# LazuriteBLE_rev1.net
KiCad netlist of a schematic drawn in EAGLE
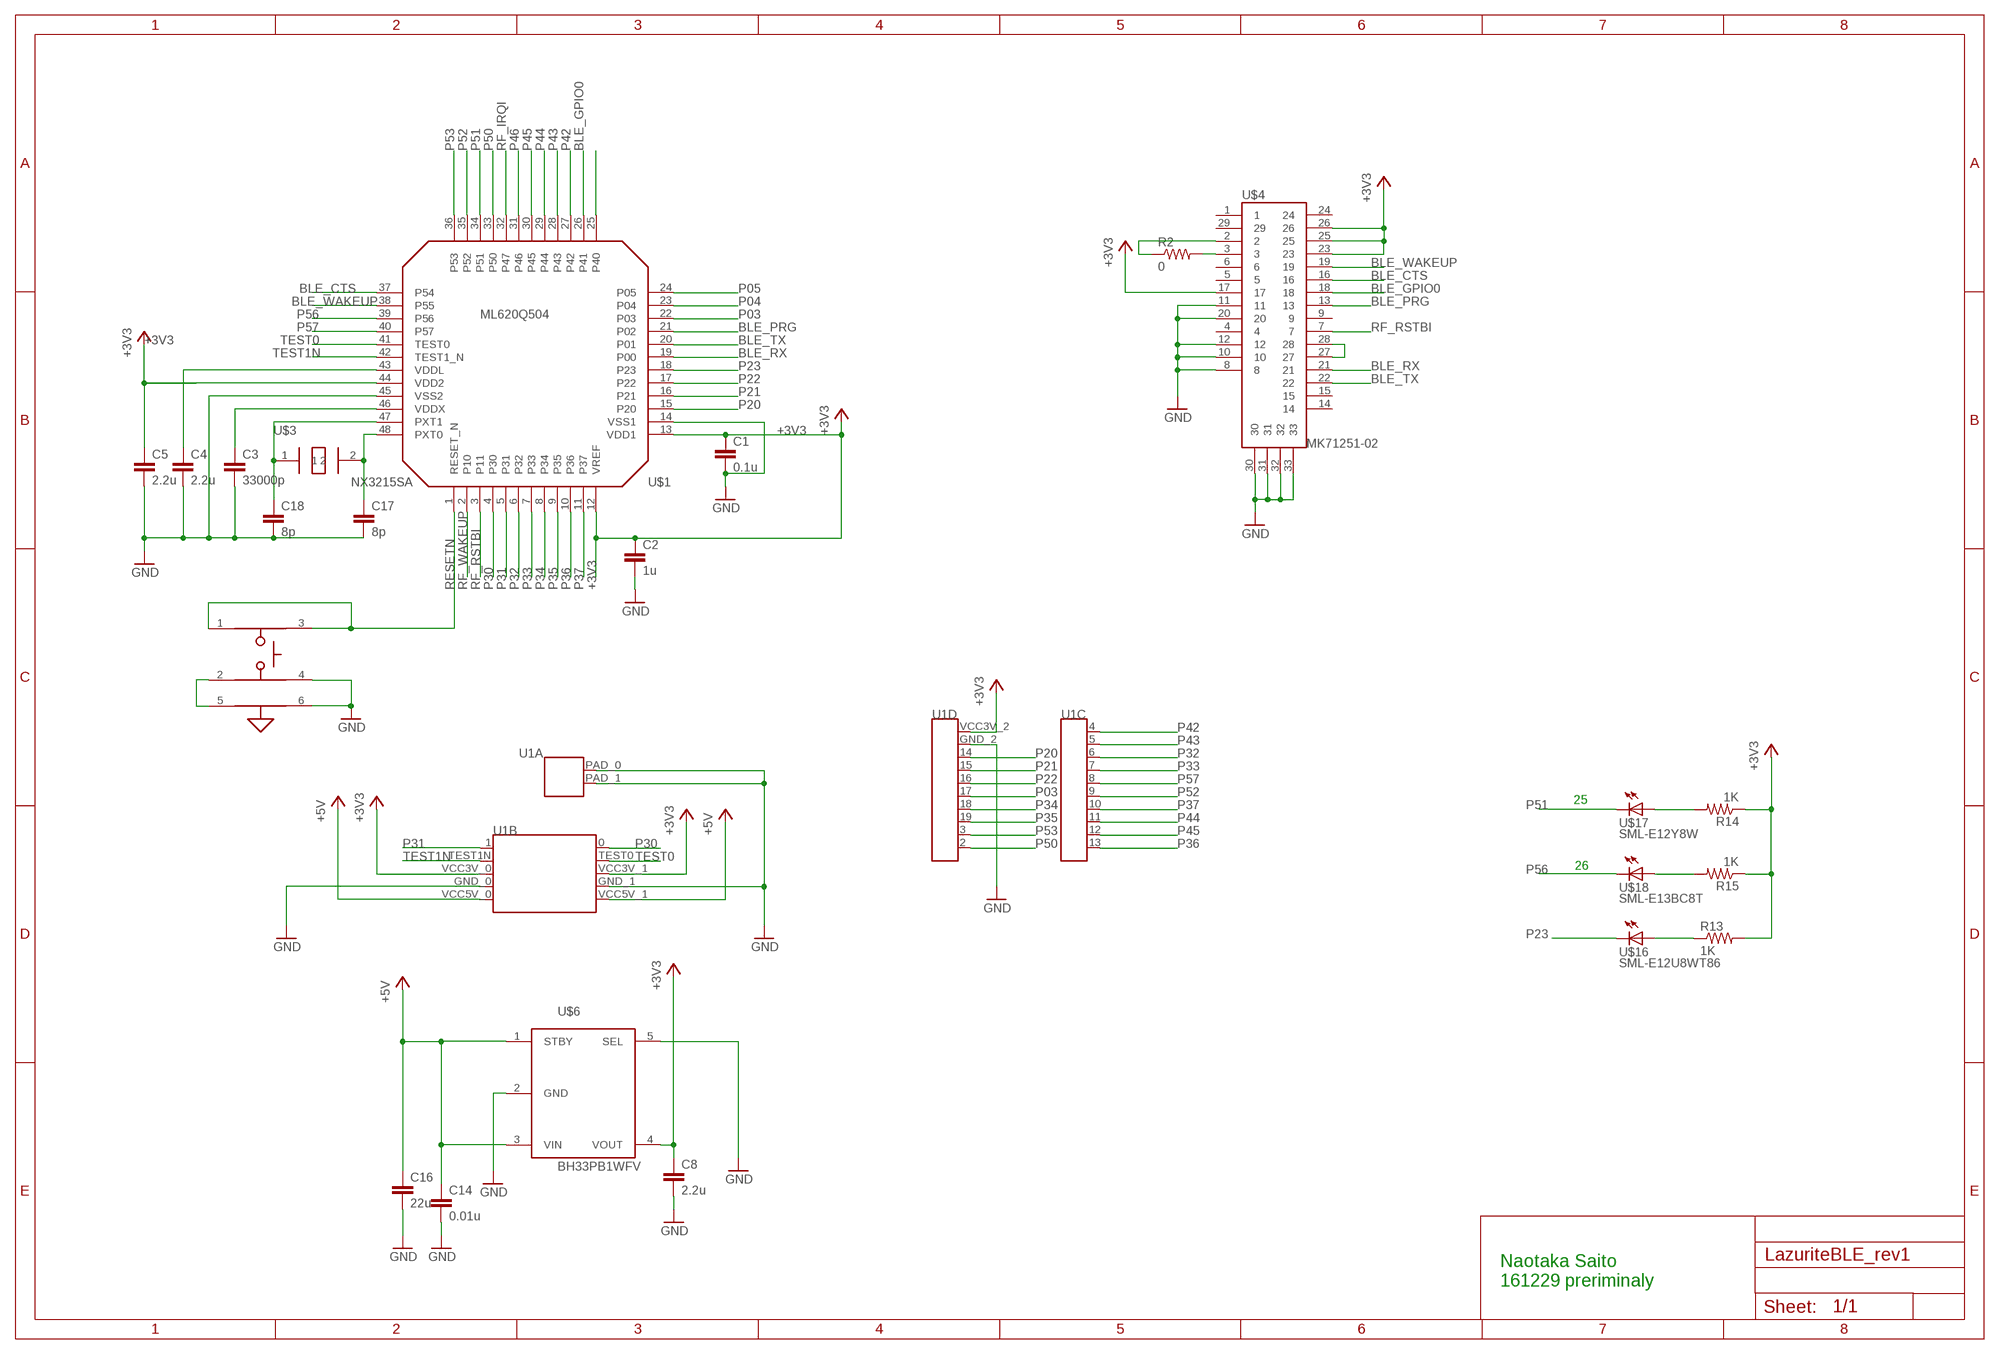
[diagram p0: schematic, sheet 1]

(export (version "E")
  (design (tool "Eeschema 10.0.6"))
  (components
    (comp (ref "C1")
      (value "0.1u")
      (footprint "eagle-import:C0402")
      (libsource (lib "eagle-import") (part "C-EUC0402"))
    )
    (comp (ref "C2")
      (value "1u")
      (footprint "eagle-import:C0402")
      (libsource (lib "eagle-import") (part "C-EUC0402"))
    )
    (comp (ref "C3")
      (value "33000p")
      (footprint "eagle-import:C0402")
      (libsource (lib "eagle-import") (part "C-EUC0402"))
    )
    (comp (ref "C4")
      (value "2.2u")
      (footprint "eagle-import:C0402")
      (libsource (lib "eagle-import") (part "C-EUC0402"))
    )
    (comp (ref "C5")
      (value "2.2u")
      (footprint "eagle-import:C0402")
      (libsource (lib "eagle-import") (part "C-EUC0402"))
    )
    (comp (ref "C8")
      (value "2.2u")
      (footprint "eagle-import:C0402")
      (libsource (lib "eagle-import") (part "C-EUC0402"))
    )
    (comp (ref "C14")
      (value "0.01u")
      (footprint "eagle-import:C0402")
      (libsource (lib "eagle-import") (part "C-EUC0402"))
    )
    (comp (ref "C16")
      (value "22u")
      (footprint "eagle-import:C1206")
      (libsource (lib "eagle-import") (part "C-EUC1206"))
    )
    (comp (ref "C17")
      (value "8p")
      (footprint "eagle-import:C0402")
      (libsource (lib "eagle-import") (part "C-EUC0402"))
    )
    (comp (ref "C18")
      (value "8p")
      (footprint "eagle-import:C0402")
      (libsource (lib "eagle-import") (part "C-EUC0402"))
    )
    (comp (ref "R2")
      (value "0")
      (footprint "eagle-import:R0402")
      (libsource (lib "eagle-import") (part "R-US_R0402"))
    )
    (comp (ref "R13")
      (value "1K")
      (footprint "eagle-import:R0402")
      (libsource (lib "eagle-import") (part "R-US_R0402"))
    )
    (comp (ref "R14")
      (value "1K")
      (footprint "eagle-import:R0402")
      (libsource (lib "eagle-import") (part "R-US_R0402"))
    )
    (comp (ref "R15")
      (value "1K")
      (footprint "eagle-import:R0402")
      (libsource (lib "eagle-import") (part "R-US_R0402"))
    )
    (comp (ref "SW1")
      (value "SKSGACE010")
      (footprint "eagle-import:SKSGACE010")
      (libsource (lib "eagle-import") (part "SKSGACE010"))
    )
    (comp (ref "U$1")
      (value "ML620Q504")
      (footprint "eagle-import:ML620Q504")
      (libsource (lib "eagle-import") (part "ML620Q504"))
    )
    (comp (ref "U$3")
      (value "NX3215SA")
      (footprint "eagle-import:NX3215SA-32,768K-SFD-MUA-14")
      (libsource (lib "eagle-import") (part "NX3215SA"))
    )
    (comp (ref "U$4")
      (value "MK71251-02")
      (footprint "eagle-import:MK71251-02")
      (libsource (lib "eagle-import") (part "MK71251-02"))
    )
    (comp (ref "U$6")
      (value "BH33PB1WFV")
      (footprint "eagle-import:HVSOF5")
      (libsource (lib "eagle-import") (part "BHXXPB1WFV"))
    )
    (comp (ref "U$16")
      (value "SML-E12U8WT86")
      (footprint "eagle-import:SML-E1X")
      (libsource (lib "eagle-import") (part "SML-E1X"))
    )
    (comp (ref "U$17")
      (value "SML-E12Y8W")
      (footprint "eagle-import:SML-E1X")
      (libsource (lib "eagle-import") (part "SML-E1X"))
    )
    (comp (ref "U$18")
      (value "SML-E13BC8T")
      (footprint "eagle-import:SML-E1X")
      (libsource (lib "eagle-import") (part "SML-E1X"))
    )
    (comp (ref "U1")
      (value "LAZURITE920J")
      (footprint "eagle-import:LAZURITE920J2")
      (libsource (lib "eagle-import") (part "LAZURITE920J"))
    )
  )
  (nets
    (net (code "1") (name "+3V3") (class "Default")
      (node (ref "C1") (pin "1") (pinfunction "1_1") (pintype "passive"))
      (node (ref "C2") (pin "1") (pinfunction "1_1") (pintype "passive"))
      (node (ref "C5") (pin "1") (pinfunction "1_1") (pintype "passive"))
      (node (ref "C8") (pin "1") (pinfunction "1_1") (pintype "passive"))
      (node (ref "R13") (pin "2") (pinfunction "2_2") (pintype "passive"))
      (node (ref "R14") (pin "1") (pinfunction "1_1") (pintype "passive"))
      (node (ref "R15") (pin "1") (pinfunction "1_1") (pintype "passive"))
      (node (ref "U$1") (pin "12") (pinfunction "VREF_12") (pintype "bidirectional"))
      (node (ref "U$1") (pin "13") (pinfunction "VDD1_13") (pintype "bidirectional"))
      (node (ref "U$1") (pin "44") (pinfunction "VDD2_44") (pintype "bidirectional"))
      (node (ref "U$4") (pin "17") (pinfunction "17_17") (pintype "power_in"))
      (node (ref "U$4") (pin "23") (pinfunction "23_23") (pintype "bidirectional"))
      (node (ref "U$4") (pin "25") (pinfunction "25_25") (pintype "bidirectional"))
      (node (ref "U$4") (pin "26") (pinfunction "26_26") (pintype "bidirectional"))
      (node (ref "U$6") (pin "4") (pinfunction "VOUT_4") (pintype "bidirectional"))
      (node (ref "U1") (pin "VCC3V_0") (pinfunction "VCC3V_0_VCC3V_0") (pintype "passive"))
      (node (ref "U1") (pin "VCC3V_1") (pinfunction "VCC3V_1_VCC3V_1") (pintype "passive"))
      (node (ref "U1") (pin "VCC3V_2") (pinfunction "VCC3V_2_VCC3V_2") (pintype "passive"))
    )
    (net (code "2") (name "+5V") (class "Default")
      (node (ref "C14") (pin "1") (pinfunction "1_1") (pintype "passive"))
      (node (ref "C16") (pin "1") (pinfunction "1_1") (pintype "passive"))
      (node (ref "U$6") (pin "1") (pinfunction "STBY_1") (pintype "bidirectional"))
      (node (ref "U$6") (pin "3") (pinfunction "VIN_3") (pintype "bidirectional"))
      (node (ref "U1") (pin "VCC5V_0") (pinfunction "VCC5V_0_VCC5V_0") (pintype "passive"))
      (node (ref "U1") (pin "VCC5V_1") (pinfunction "VCC5V_1_VCC5V_1") (pintype "passive"))
    )
    (net (code "3") (name "/BLE_CTS") (class "Default")
      (node (ref "U$1") (pin "37") (pinfunction "P54_37") (pintype "bidirectional"))
      (node (ref "U$4") (pin "16") (pinfunction "16_16") (pintype "bidirectional"))
    )
    (net (code "4") (name "/BLE_GPIO0") (class "Default")
      (node (ref "U$1") (pin "26") (pinfunction "P41_26") (pintype "bidirectional"))
      (node (ref "U$4") (pin "18") (pinfunction "18_18") (pintype "bidirectional"))
    )
    (net (code "5") (name "/BLE_PRG") (class "Default")
      (node (ref "U$1") (pin "21") (pinfunction "P02_21") (pintype "bidirectional"))
      (node (ref "U$4") (pin "13") (pinfunction "13_13") (pintype "bidirectional"))
    )
    (net (code "6") (name "/BLE_RX") (class "Default")
      (node (ref "U$1") (pin "19") (pinfunction "P00_19") (pintype "bidirectional"))
      (node (ref "U$4") (pin "21") (pinfunction "21_21") (pintype "bidirectional"))
    )
    (net (code "7") (name "/BLE_TX") (class "Default")
      (node (ref "U$1") (pin "20") (pinfunction "P01_20") (pintype "bidirectional"))
      (node (ref "U$4") (pin "22") (pinfunction "22_22") (pintype "bidirectional"))
    )
    (net (code "8") (name "/BLE_WAKEUP") (class "Default")
      (node (ref "U$1") (pin "38") (pinfunction "P55_38") (pintype "bidirectional"))
      (node (ref "U$4") (pin "19") (pinfunction "19_19") (pintype "input"))
    )
    (net (code "9") (name "/P03") (class "Default")
      (node (ref "U$1") (pin "22") (pinfunction "P03_22") (pintype "bidirectional"))
      (node (ref "U1") (pin "17") (pinfunction "17_17") (pintype "passive"))
    )
    (net (code "10") (name "/P04") (class "Default")
      (node (ref "U$1") (pin "23") (pinfunction "P04_23") (pintype "bidirectional"))
    )
    (net (code "11") (name "/P05") (class "Default")
      (node (ref "U$1") (pin "24") (pinfunction "P05_24") (pintype "bidirectional"))
    )
    (net (code "12") (name "/P20") (class "Default")
      (node (ref "U$1") (pin "15") (pinfunction "P20_15") (pintype "bidirectional"))
      (node (ref "U1") (pin "14") (pinfunction "14_14") (pintype "passive"))
    )
    (net (code "13") (name "/P21") (class "Default")
      (node (ref "U$1") (pin "16") (pinfunction "P21_16") (pintype "bidirectional"))
      (node (ref "U1") (pin "15") (pinfunction "15_15") (pintype "passive"))
    )
    (net (code "14") (name "/P22") (class "Default")
      (node (ref "U$1") (pin "17") (pinfunction "P22_17") (pintype "bidirectional"))
      (node (ref "U1") (pin "16") (pinfunction "16_16") (pintype "passive"))
    )
    (net (code "15") (name "/P23") (class "Default")
      (node (ref "U$1") (pin "18") (pinfunction "P23_18") (pintype "bidirectional"))
      (node (ref "U$16") (pin "C") (pinfunction "C_C") (pintype "passive"))
    )
    (net (code "16") (name "/P30") (class "Default")
      (node (ref "U$1") (pin "4") (pinfunction "P30_4") (pintype "bidirectional"))
      (node (ref "U1") (pin "0") (pinfunction "0_0") (pintype "passive"))
    )
    (net (code "17") (name "/P31") (class "Default")
      (node (ref "U$1") (pin "5") (pinfunction "P31_5") (pintype "bidirectional"))
      (node (ref "U1") (pin "1") (pinfunction "1_1") (pintype "passive"))
    )
    (net (code "18") (name "/P32") (class "Default")
      (node (ref "U$1") (pin "6") (pinfunction "P32_6") (pintype "bidirectional"))
      (node (ref "U1") (pin "6") (pinfunction "6_6") (pintype "passive"))
    )
    (net (code "19") (name "/P33") (class "Default")
      (node (ref "U$1") (pin "7") (pinfunction "P33_7") (pintype "bidirectional"))
      (node (ref "U1") (pin "7") (pinfunction "7_7") (pintype "passive"))
    )
    (net (code "20") (name "/P34") (class "Default")
      (node (ref "U$1") (pin "8") (pinfunction "P34_8") (pintype "bidirectional"))
      (node (ref "U1") (pin "18") (pinfunction "18_18") (pintype "passive"))
    )
    (net (code "21") (name "/P35") (class "Default")
      (node (ref "U$1") (pin "9") (pinfunction "P35_9") (pintype "bidirectional"))
      (node (ref "U1") (pin "19") (pinfunction "19_19") (pintype "passive"))
    )
    (net (code "22") (name "/P36") (class "Default")
      (node (ref "U$1") (pin "10") (pinfunction "P36_10") (pintype "bidirectional"))
      (node (ref "U1") (pin "13") (pinfunction "13_13") (pintype "passive"))
    )
    (net (code "23") (name "/P37") (class "Default")
      (node (ref "U$1") (pin "11") (pinfunction "P37_11") (pintype "bidirectional"))
      (node (ref "U1") (pin "10") (pinfunction "10_10") (pintype "passive"))
    )
    (net (code "24") (name "/P42") (class "Default")
      (node (ref "U$1") (pin "27") (pinfunction "P42_27") (pintype "bidirectional"))
      (node (ref "U1") (pin "4") (pinfunction "4_4") (pintype "passive"))
    )
    (net (code "25") (name "/P43") (class "Default")
      (node (ref "U$1") (pin "28") (pinfunction "P43_28") (pintype "bidirectional"))
      (node (ref "U1") (pin "5") (pinfunction "5_5") (pintype "passive"))
    )
    (net (code "26") (name "/P44") (class "Default")
      (node (ref "U$1") (pin "29") (pinfunction "P44_29") (pintype "bidirectional"))
      (node (ref "U1") (pin "11") (pinfunction "11_11") (pintype "passive"))
    )
    (net (code "27") (name "/P45") (class "Default")
      (node (ref "U$1") (pin "30") (pinfunction "P45_30") (pintype "bidirectional"))
      (node (ref "U1") (pin "12") (pinfunction "12_12") (pintype "passive"))
    )
    (net (code "28") (name "/P46") (class "Default")
      (node (ref "U$1") (pin "31") (pinfunction "P46_31") (pintype "bidirectional"))
    )
    (net (code "29") (name "/P50") (class "Default")
      (node (ref "U$1") (pin "33") (pinfunction "P50_33") (pintype "bidirectional"))
      (node (ref "U1") (pin "2") (pinfunction "2_2") (pintype "passive"))
    )
    (net (code "30") (name "/P51") (class "Default")
      (node (ref "U$1") (pin "34") (pinfunction "P51_34") (pintype "bidirectional"))
      (node (ref "U$17") (pin "C") (pinfunction "C_C") (pintype "passive"))
    )
    (net (code "31") (name "/P52") (class "Default")
      (node (ref "U$1") (pin "35") (pinfunction "P52_35") (pintype "bidirectional"))
      (node (ref "U1") (pin "9") (pinfunction "9_9") (pintype "passive"))
    )
    (net (code "32") (name "/P53") (class "Default")
      (node (ref "U$1") (pin "36") (pinfunction "P53_36") (pintype "bidirectional"))
      (node (ref "U1") (pin "3") (pinfunction "3_3") (pintype "passive"))
    )
    (net (code "33") (name "/P56") (class "Default")
      (node (ref "U$1") (pin "39") (pinfunction "P56_39") (pintype "bidirectional"))
      (node (ref "U$18") (pin "C") (pinfunction "C_C") (pintype "passive"))
    )
    (net (code "34") (name "/P57") (class "Default")
      (node (ref "U$1") (pin "40") (pinfunction "P57_40") (pintype "bidirectional"))
      (node (ref "U1") (pin "8") (pinfunction "8_8") (pintype "passive"))
    )
    (net (code "35") (name "/RESETN") (class "Default")
      (node (ref "SW1") (pin "1") (pinfunction "1_1") (pintype "bidirectional"))
      (node (ref "SW1") (pin "3") (pinfunction "3_3") (pintype "bidirectional"))
      (node (ref "U$1") (pin "1") (pinfunction "RESET_N_1") (pintype "bidirectional"))
    )
    (net (code "36") (name "/RF_IRQI") (class "Default")
      (node (ref "U$1") (pin "32") (pinfunction "P47_32") (pintype "bidirectional"))
    )
    (net (code "37") (name "/RF_RSTBI") (class "Default")
      (node (ref "U$1") (pin "3") (pinfunction "P11_3") (pintype "bidirectional"))
      (node (ref "U$4") (pin "7") (pinfunction "7_7") (pintype "input"))
    )
    (net (code "38") (name "/RF_WAKEUP") (class "Default")
      (node (ref "U$1") (pin "2") (pinfunction "P10_2") (pintype "bidirectional"))
    )
    (net (code "39") (name "/TEST0") (class "Default")
      (node (ref "U$1") (pin "41") (pinfunction "TEST0_41") (pintype "bidirectional"))
      (node (ref "U1") (pin "TEST0") (pinfunction "TEST0_TEST0") (pintype "passive"))
    )
    (net (code "40") (name "/TEST1N") (class "Default")
      (node (ref "U$1") (pin "42") (pinfunction "TEST1_N_42") (pintype "bidirectional"))
      (node (ref "U1") (pin "TEST1N") (pinfunction "TEST1N_TEST1N") (pintype "passive"))
    )
    (net (code "41") (name "GND") (class "Default")
      (node (ref "C1") (pin "2") (pinfunction "2_2") (pintype "passive"))
      (node (ref "C14") (pin "2") (pinfunction "2_2") (pintype "passive"))
      (node (ref "C16") (pin "2") (pinfunction "2_2") (pintype "passive"))
      (node (ref "C17") (pin "2") (pinfunction "2_2") (pintype "passive"))
      (node (ref "C18") (pin "2") (pinfunction "2_2") (pintype "passive"))
      (node (ref "C2") (pin "2") (pinfunction "2_2") (pintype "passive"))
      (node (ref "C3") (pin "2") (pinfunction "2_2") (pintype "passive"))
      (node (ref "C4") (pin "2") (pinfunction "2_2") (pintype "passive"))
      (node (ref "C5") (pin "2") (pinfunction "2_2") (pintype "passive"))
      (node (ref "C8") (pin "2") (pinfunction "2_2") (pintype "passive"))
      (node (ref "SW1") (pin "4") (pinfunction "4_4") (pintype "bidirectional"))
      (node (ref "SW1") (pin "6") (pinfunction "6_6") (pintype "power_in"))
      (node (ref "U$1") (pin "14") (pinfunction "VSS1_14") (pintype "bidirectional"))
      (node (ref "U$1") (pin "45") (pinfunction "VSS2_45") (pintype "bidirectional"))
      (node (ref "U$4") (pin "10") (pinfunction "10_10") (pintype "input"))
      (node (ref "U$4") (pin "11") (pinfunction "11_11") (pintype "bidirectional"))
      (node (ref "U$4") (pin "12") (pinfunction "12_12") (pintype "input"))
      (node (ref "U$4") (pin "20") (pinfunction "20_20") (pintype "bidirectional"))
      (node (ref "U$4") (pin "30") (pinfunction "30_30") (pintype "power_in"))
      (node (ref "U$4") (pin "31") (pinfunction "31_31") (pintype "power_in"))
      (node (ref "U$4") (pin "32") (pinfunction "32_32") (pintype "power_in"))
      (node (ref "U$4") (pin "33") (pinfunction "33_33") (pintype "power_in"))
      (node (ref "U$4") (pin "8") (pinfunction "8_8") (pintype "input"))
      (node (ref "U$6") (pin "2") (pinfunction "GND_2") (pintype "bidirectional"))
      (node (ref "U$6") (pin "5") (pinfunction "SEL_5") (pintype "bidirectional"))
      (node (ref "U1") (pin "GND_0") (pinfunction "GND_0_GND_0") (pintype "passive"))
      (node (ref "U1") (pin "GND_1") (pinfunction "GND_1_GND_1") (pintype "passive"))
      (node (ref "U1") (pin "GND_2") (pinfunction "GND_2_GND_2") (pintype "passive"))
      (node (ref "U1") (pin "PAD_0") (pinfunction "PAD_0_PAD_0") (pintype "passive"))
      (node (ref "U1") (pin "PAD_1") (pinfunction "PAD_1_PAD_1") (pintype "passive"))
    )
    (net (code "42") (name "Net-(R2-Pad1)") (class "Default")
      (node (ref "R2") (pin "1") (pinfunction "1_1") (pintype "passive"))
      (node (ref "U$4") (pin "2") (pinfunction "2_2") (pintype "input"))
    )
    (net (code "43") (name "Net-(R2-Pad2)") (class "Default")
      (node (ref "R2") (pin "2") (pinfunction "2_2") (pintype "passive"))
      (node (ref "U$4") (pin "3") (pinfunction "3_3") (pintype "bidirectional"))
    )
    (net (code "44") (name "Net-(R13-Pad1)") (class "Default")
      (node (ref "R13") (pin "1") (pinfunction "1_1") (pintype "passive"))
      (node (ref "U$16") (pin "A") (pinfunction "A_A") (pintype "passive"))
    )
    (net (code "45") (name "Net-(R14-Pad2)") (class "Default")
      (node (ref "R14") (pin "2") (pinfunction "2_2") (pintype "passive"))
      (node (ref "U$17") (pin "A") (pinfunction "A_A") (pintype "passive"))
    )
    (net (code "46") (name "Net-(R15-Pad2)") (class "Default")
      (node (ref "R15") (pin "2") (pinfunction "2_2") (pintype "passive"))
      (node (ref "U$18") (pin "A") (pinfunction "A_A") (pintype "passive"))
    )
    (net (code "47") (name "Net-(SW1-Pad2)") (class "Default")
      (node (ref "SW1") (pin "2") (pinfunction "2_2") (pintype "bidirectional"))
      (node (ref "SW1") (pin "5") (pinfunction "5_5") (pintype "power_in"))
    )
    (net (code "48") (name "Net-(U$1-PXT0)") (class "Default")
      (node (ref "C17") (pin "1") (pinfunction "1_1") (pintype "passive"))
      (node (ref "U$1") (pin "48") (pinfunction "PXT0_48") (pintype "bidirectional"))
      (node (ref "U$3") (pin "2") (pinfunction "2_2") (pintype "bidirectional"))
    )
    (net (code "49") (name "Net-(U$1-PXT1)") (class "Default")
      (node (ref "C18") (pin "1") (pinfunction "1_1") (pintype "passive"))
      (node (ref "U$1") (pin "47") (pinfunction "PXT1_47") (pintype "bidirectional"))
      (node (ref "U$3") (pin "1") (pinfunction "1_1") (pintype "bidirectional"))
    )
    (net (code "50") (name "Net-(U$1-VDDL)") (class "Default")
      (node (ref "C4") (pin "1") (pinfunction "1_1") (pintype "passive"))
      (node (ref "U$1") (pin "43") (pinfunction "VDDL_43") (pintype "bidirectional"))
    )
    (net (code "51") (name "Net-(U$1-VDDX)") (class "Default")
      (node (ref "C3") (pin "1") (pinfunction "1_1") (pintype "passive"))
      (node (ref "U$1") (pin "46") (pinfunction "VDDX_46") (pintype "bidirectional"))
    )
    (net (code "52") (name "Net-(U$4-Pad27)") (class "Default")
      (node (ref "U$4") (pin "27") (pinfunction "27_27") (pintype "bidirectional"))
      (node (ref "U$4") (pin "28") (pinfunction "28_28") (pintype "bidirectional"))
    )
    (net (code "53") (name "unconnected-(U$1-P40-Pad25)") (class "Default")
      (node (ref "U$1") (pin "25") (pinfunction "P40_25") (pintype "bidirectional"))
    )
    (net (code "54") (name "unconnected-(U$4-Pad1)") (class "Default")
      (node (ref "U$4") (pin "1") (pinfunction "1_1") (pintype "no_connect"))
    )
    (net (code "55") (name "unconnected-(U$4-Pad4)") (class "Default")
      (node (ref "U$4") (pin "4") (pinfunction "4_4") (pintype "bidirectional"))
    )
    (net (code "56") (name "unconnected-(U$4-Pad5)") (class "Default")
      (node (ref "U$4") (pin "5") (pinfunction "5_5") (pintype "bidirectional"))
    )
    (net (code "57") (name "unconnected-(U$4-Pad6)") (class "Default")
      (node (ref "U$4") (pin "6") (pinfunction "6_6") (pintype "bidirectional"))
    )
    (net (code "58") (name "unconnected-(U$4-Pad9)") (class "Default")
      (node (ref "U$4") (pin "9") (pinfunction "9_9") (pintype "bidirectional"))
    )
    (net (code "59") (name "unconnected-(U$4-Pad14)") (class "Default")
      (node (ref "U$4") (pin "14") (pinfunction "14_14") (pintype "bidirectional"))
    )
    (net (code "60") (name "unconnected-(U$4-Pad15)") (class "Default")
      (node (ref "U$4") (pin "15") (pinfunction "15_15") (pintype "bidirectional"))
    )
    (net (code "61") (name "unconnected-(U$4-Pad24)") (class "Default")
      (node (ref "U$4") (pin "24") (pinfunction "24_24") (pintype "bidirectional"))
    )
    (net (code "62") (name "unconnected-(U$4-Pad29)") (class "Default")
      (node (ref "U$4") (pin "29") (pinfunction "29_29") (pintype "no_connect"))
    )
  )
)
